# ChangeOverSwitch.net
KiCad netlist of a schematic drawn in EAGLE
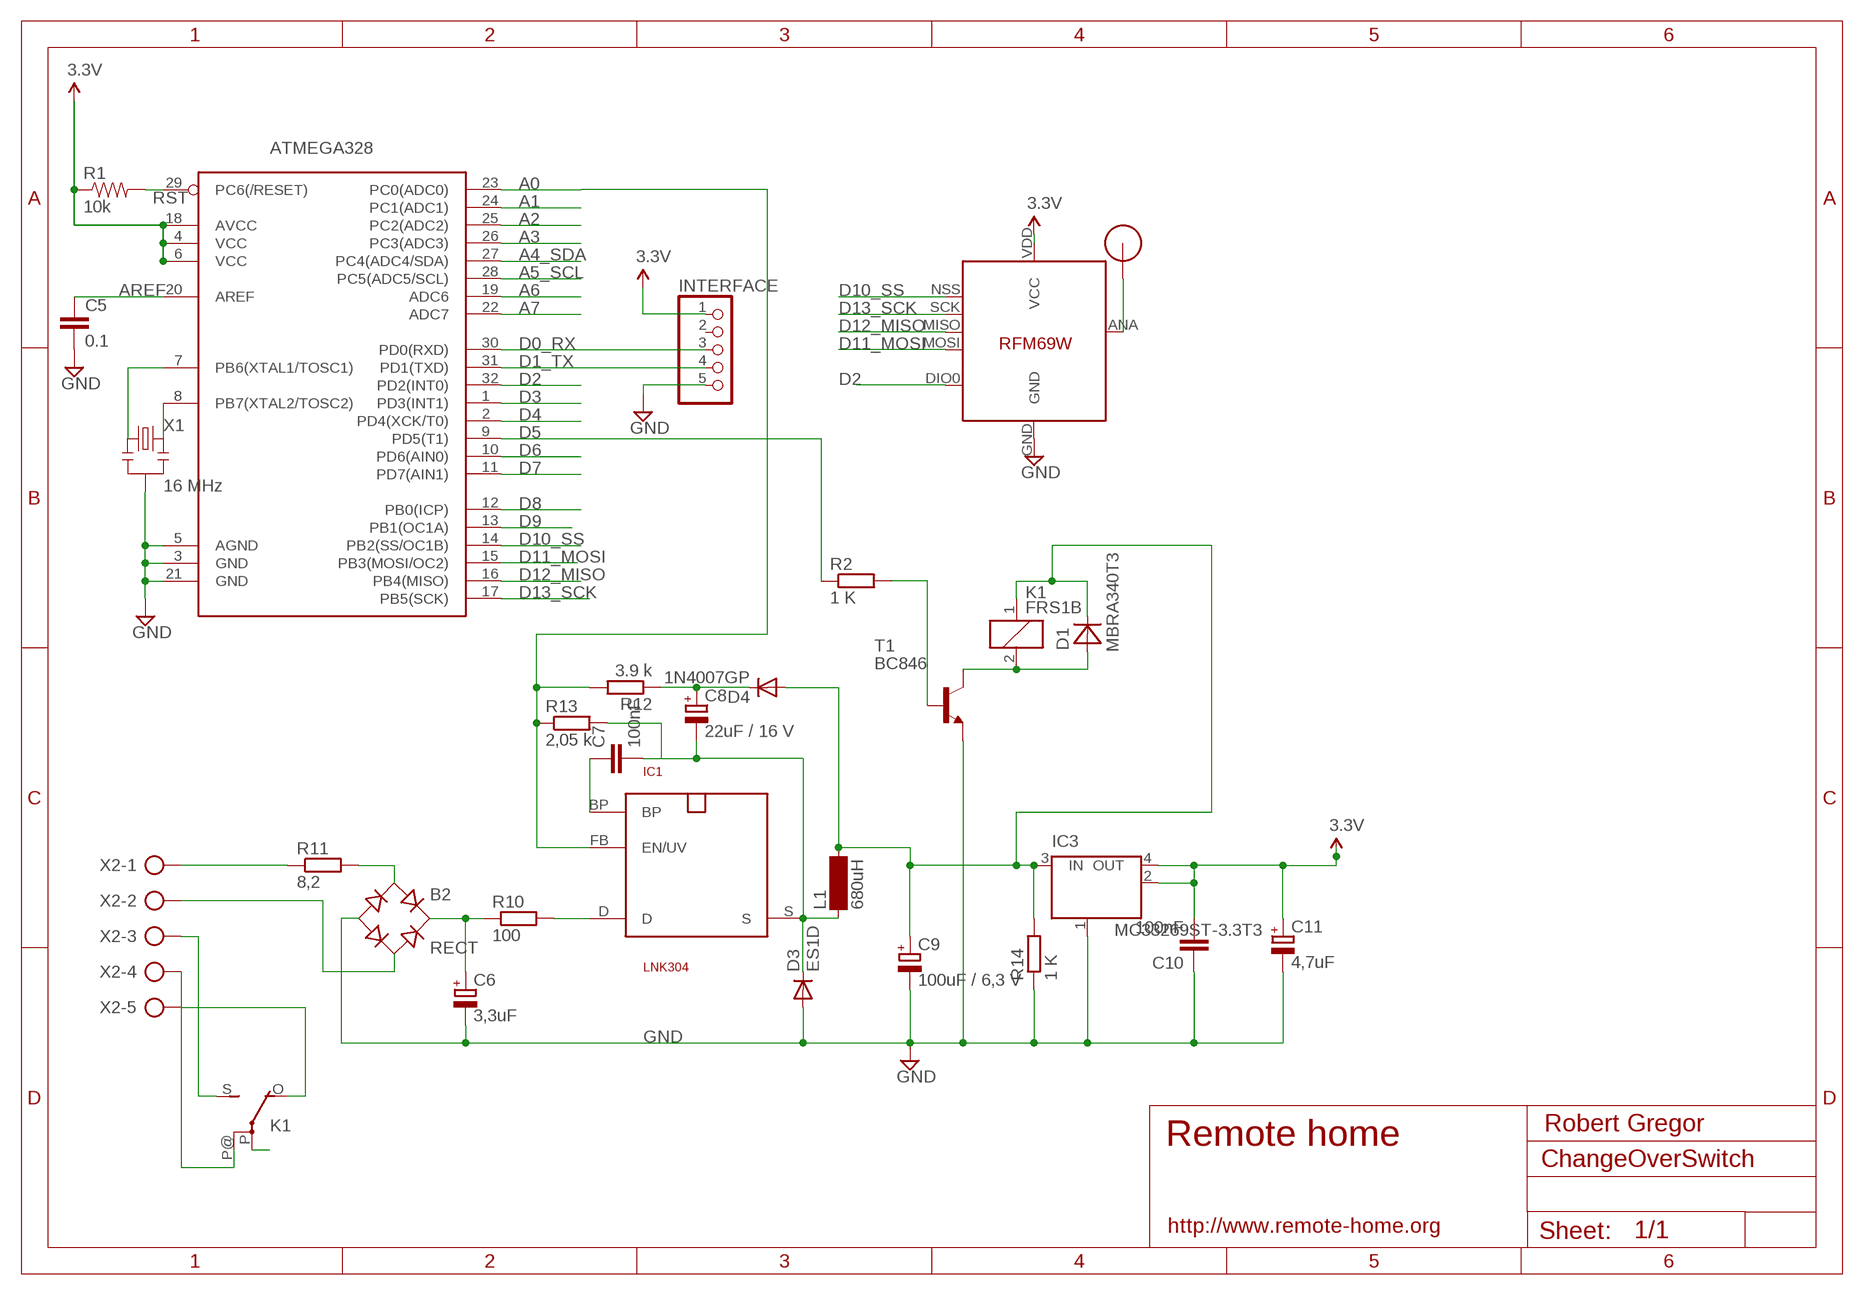
[diagram p0: schematic, sheet 1]

(export (version "E")
  (design (tool "Eeschema 10.0.6"))
  (components
    (comp (ref "ATMEGA328")
      (value "ATMega-328")
      (footprint "eagle-import:TQFP32-08")
      (libsource (lib "eagle-import") (part "ATMEGA168/328TQFP32"))
    )
    (comp (ref "B2")
      (value "RECT")
      (footprint "eagle-import:TO-269AA")
      (libsource (lib "eagle-import") (part "RECTIFIER-S40"))
    )
    (comp (ref "C5")
      (value "0.1")
      (footprint "eagle-import:0603-CAP")
      (libsource (lib "eagle-import") (part "CAP0603-CAP"))
    )
    (comp (ref "C6")
      (value "3,3uF")
      (footprint "eagle-import:E5-10,5")
      (libsource (lib "eagle-import") (part "CPOL-EUE5-10.5"))
    )
    (comp (ref "C7")
      (value "100nF")
      (footprint "eagle-import:C2012")
      (libsource (lib "eagle-import") (part "C-EUC2012"))
    )
    (comp (ref "C8")
      (value "22uF / 16 V")
      (footprint "eagle-import:SMC_C")
      (libsource (lib "eagle-import") (part "CPOL-EUSMCC"))
    )
    (comp (ref "C9")
      (value "100uF / 6,3 V")
      (footprint "eagle-import:E2,5-5")
      (libsource (lib "eagle-import") (part "CPOL-EUE2.5-5"))
    )
    (comp (ref "C10")
      (value "100nF")
      (footprint "eagle-import:C2012")
      (libsource (lib "eagle-import") (part "C-EUC2012"))
    )
    (comp (ref "C11")
      (value "4,7uF")
      (footprint "eagle-import:SMC_A")
      (libsource (lib "eagle-import") (part "CPOL-EUSMCA"))
    )
    (comp (ref "D1")
      (value "MBRA340T3")
      (footprint "eagle-import:SMA")
      (libsource (lib "eagle-import") (part "MBRA340T3"))
    )
    (comp (ref "D3")
      (value "ES1D")
      (footprint "eagle-import:DO214AC")
      (libsource (lib "eagle-import") (part "DIODE-DO214AC"))
    )
    (comp (ref "D4")
      (value "1N4007GP")
      (footprint "eagle-import:DO214AA")
      (libsource (lib "eagle-import") (part "DIODE-DO214AA"))
    )
    (comp (ref "IC1")
      (value "LNK304")
      (footprint "eagle-import:SO-8C")
      (libsource (lib "eagle-import") (part "SO-8C"))
    )
    (comp (ref "IC3")
      (value "MC33269ST-3.3T3")
      (footprint "eagle-import:SOT223")
      (libsource (lib "eagle-import") (part "MC33269ST-3.3T3"))
    )
    (comp (ref "INTERFACE")
      (value "PINHD-1X5")
      (footprint "eagle-import:1X05")
      (libsource (lib "eagle-import") (part "PINHD-1X5"))
    )
    (comp (ref "K1")
      (value "FRS1B")
      (footprint "eagle-import:FRS1B")
      (libsource (lib "eagle-import") (part "FRS1B"))
    )
    (comp (ref "L1")
      (value "680uH")
      (footprint "eagle-import:BS11")
      (libsource (lib "eagle-import") (part "BS11"))
    )
    (comp (ref "R1")
      (value "10k")
      (footprint "eagle-import:0603-RES")
      (libsource (lib "eagle-import") (part "RESISTOR0603-RES"))
    )
    (comp (ref "R2")
      (value "1 K")
      (footprint "eagle-import:M2012")
      (libsource (lib "eagle-import") (part "R-EU_M2012"))
    )
    (comp (ref "R10")
      (value "100")
      (footprint "eagle-import:R2512W")
      (libsource (lib "eagle-import") (part "R-EU_R2512W"))
    )
    (comp (ref "R11")
      (value "8,2")
      (footprint "eagle-import:0411_12")
      (libsource (lib "eagle-import") (part "R-EU_0411/12"))
    )
    (comp (ref "R12")
      (value "3.9 k")
      (footprint "eagle-import:M2012")
      (libsource (lib "eagle-import") (part "R-EU_M2012"))
    )
    (comp (ref "R13")
      (value "2,05 k")
      (footprint "eagle-import:M2012")
      (libsource (lib "eagle-import") (part "R-EU_M2012"))
    )
    (comp (ref "R14")
      (value "1 K")
      (footprint "eagle-import:M2012")
      (libsource (lib "eagle-import") (part "R-EU_M2012"))
    )
    (comp (ref "T1")
      (value "BC846")
      (footprint "eagle-import:SOT23")
      (libsource (lib "eagle-import") (part "BC846"))
    )
    (comp (ref "U$1")
      (value "RFM12B_ANTENNA")
      (footprint "eagle-import:RFM12B-ANTENNA")
      (libsource (lib "eagle-import") (part "RFM12B_ANTENNA"))
    )
    (comp (ref "U$5")
      (value "RFM69")
      (footprint "eagle-import:RFM69W-MINPADS")
      (libsource (lib "eagle-import") (part "RFM69"))
    )
    (comp (ref "X1")
      (value "16 MHz")
      (footprint "eagle-import:RESONATOR-SMD")
      (libsource (lib "eagle-import") (part "RESONATORSMD"))
    )
    (comp (ref "X2")
      (value "AK500/5")
      (footprint "eagle-import:AK500_5")
      (libsource (lib "eagle-import") (part "AK500/5"))
    )
  )
  (nets
    (net (code "1") (name "/A0") (class "Default")
      (node (ref "ATMEGA328") (pin "23") (pinfunction "PC0(ADC0)_23") (pintype "bidirectional"))
      (node (ref "IC1") (pin "FB") (pinfunction "EN/UV_FB") (pintype "input"))
      (node (ref "R12") (pin "2") (pinfunction "2_2") (pintype "passive"))
      (node (ref "R13") (pin "1") (pinfunction "1_1") (pintype "passive"))
    )
    (net (code "2") (name "/A1") (class "Default")
      (node (ref "ATMEGA328") (pin "24") (pinfunction "PC1(ADC1)_24") (pintype "bidirectional"))
    )
    (net (code "3") (name "/A2") (class "Default")
      (node (ref "ATMEGA328") (pin "25") (pinfunction "PC2(ADC2)_25") (pintype "bidirectional"))
    )
    (net (code "4") (name "/A3") (class "Default")
      (node (ref "ATMEGA328") (pin "26") (pinfunction "PC3(ADC3)_26") (pintype "bidirectional"))
    )
    (net (code "5") (name "/A4_SDA") (class "Default")
      (node (ref "ATMEGA328") (pin "27") (pinfunction "PC4(ADC4/SDA)_27") (pintype "bidirectional"))
    )
    (net (code "6") (name "/A5_SCL") (class "Default")
      (node (ref "ATMEGA328") (pin "28") (pinfunction "PC5(ADC5/SCL)_28") (pintype "bidirectional"))
    )
    (net (code "7") (name "/A6") (class "Default")
      (node (ref "ATMEGA328") (pin "19") (pinfunction "ADC6_19") (pintype "bidirectional"))
    )
    (net (code "8") (name "/A7") (class "Default")
      (node (ref "ATMEGA328") (pin "22") (pinfunction "ADC7_22") (pintype "bidirectional"))
    )
    (net (code "9") (name "/AREF") (class "Default")
      (node (ref "ATMEGA328") (pin "20") (pinfunction "AREF_20") (pintype "bidirectional"))
      (node (ref "C5") (pin "1") (pinfunction "1_1") (pintype "passive"))
    )
    (net (code "10") (name "/D0_RX") (class "Default")
      (node (ref "ATMEGA328") (pin "30") (pinfunction "PD0(RXD)_30") (pintype "bidirectional"))
      (node (ref "INTERFACE") (pin "3") (pinfunction "3_3") (pintype "passive"))
    )
    (net (code "11") (name "/D1_TX") (class "Default")
      (node (ref "ATMEGA328") (pin "31") (pinfunction "PD1(TXD)_31") (pintype "bidirectional"))
      (node (ref "INTERFACE") (pin "4") (pinfunction "4_4") (pintype "passive"))
    )
    (net (code "12") (name "/D2") (class "Default")
      (node (ref "ATMEGA328") (pin "32") (pinfunction "PD2(INT0)_32") (pintype "bidirectional"))
      (node (ref "U$5") (pin "DIO0") (pinfunction "DIO0_DIO0") (pintype "open_collector"))
    )
    (net (code "13") (name "/D3") (class "Default")
      (node (ref "ATMEGA328") (pin "1") (pinfunction "PD3(INT1)_1") (pintype "bidirectional"))
    )
    (net (code "14") (name "/D4") (class "Default")
      (node (ref "ATMEGA328") (pin "2") (pinfunction "PD4(XCK/T0)_2") (pintype "bidirectional"))
    )
    (net (code "15") (name "/D5") (class "Default")
      (node (ref "ATMEGA328") (pin "9") (pinfunction "PD5(T1)_9") (pintype "bidirectional"))
      (node (ref "R2") (pin "1") (pinfunction "1_1") (pintype "passive"))
    )
    (net (code "16") (name "/D6") (class "Default")
      (node (ref "ATMEGA328") (pin "10") (pinfunction "PD6(AIN0)_10") (pintype "bidirectional"))
    )
    (net (code "17") (name "/D7") (class "Default")
      (node (ref "ATMEGA328") (pin "11") (pinfunction "PD7(AIN1)_11") (pintype "bidirectional"))
    )
    (net (code "18") (name "/D8") (class "Default")
      (node (ref "ATMEGA328") (pin "12") (pinfunction "PB0(ICP)_12") (pintype "bidirectional"))
    )
    (net (code "19") (name "/D9") (class "Default")
      (node (ref "ATMEGA328") (pin "13") (pinfunction "PB1(OC1A)_13") (pintype "bidirectional"))
    )
    (net (code "20") (name "/D10_SS") (class "Default")
      (node (ref "ATMEGA328") (pin "14") (pinfunction "PB2(SS/OC1B)_14") (pintype "bidirectional"))
      (node (ref "U$5") (pin "NSS") (pinfunction "SEL_NSS") (pintype "input"))
    )
    (net (code "21") (name "/D11_MOSI") (class "Default")
      (node (ref "ATMEGA328") (pin "15") (pinfunction "PB3(MOSI/OC2)_15") (pintype "bidirectional"))
      (node (ref "U$5") (pin "MOSI") (pinfunction "MOSI_MOSI") (pintype "output"))
    )
    (net (code "22") (name "/D12_MISO") (class "Default")
      (node (ref "ATMEGA328") (pin "16") (pinfunction "PB4(MISO)_16") (pintype "bidirectional"))
      (node (ref "U$5") (pin "MISO") (pinfunction "MISO_MISO") (pintype "input"))
    )
    (net (code "23") (name "/D13_SCK") (class "Default")
      (node (ref "ATMEGA328") (pin "17") (pinfunction "PB5(SCK)_17") (pintype "bidirectional"))
      (node (ref "U$5") (pin "SCK") (pinfunction "SCK_SCK") (pintype "input"))
    )
    (net (code "24") (name "/RST") (class "Default")
      (node (ref "ATMEGA328") (pin "29") (pinfunction "PC6(/RESET)_29") (pintype "bidirectional"))
      (node (ref "R1") (pin "2") (pinfunction "2_2") (pintype "passive"))
    )
    (net (code "25") (name "3.3V") (class "Default")
      (node (ref "ATMEGA328") (pin "18") (pinfunction "AVCC_18") (pintype "bidirectional"))
      (node (ref "ATMEGA328") (pin "4") (pinfunction "VCC_4") (pintype "bidirectional"))
      (node (ref "ATMEGA328") (pin "6") (pinfunction "VCC_6") (pintype "bidirectional"))
      (node (ref "C10") (pin "2") (pinfunction "2_2") (pintype "passive"))
      (node (ref "C11") (pin "+") (pinfunction "+_+") (pintype "passive"))
      (node (ref "IC3") (pin "2") (pinfunction "OUT_2") (pintype "passive"))
      (node (ref "IC3") (pin "4") (pinfunction "OUT_4") (pintype "passive"))
      (node (ref "INTERFACE") (pin "1") (pinfunction "1_1") (pintype "passive"))
      (node (ref "R1") (pin "1") (pinfunction "1_1") (pintype "passive"))
      (node (ref "U$5") (pin "VDD") (pinfunction "VCC_VDD") (pintype "power_in"))
    )
    (net (code "26") (name "GND") (class "Default")
      (node (ref "ATMEGA328") (pin "21") (pinfunction "GND_21") (pintype "bidirectional"))
      (node (ref "ATMEGA328") (pin "3") (pinfunction "GND_3") (pintype "bidirectional"))
      (node (ref "ATMEGA328") (pin "5") (pinfunction "AGND_5") (pintype "bidirectional"))
      (node (ref "B2") (pin "-") (pinfunction "-_-") (pintype "passive"))
      (node (ref "C10") (pin "1") (pinfunction "1_1") (pintype "passive"))
      (node (ref "C11") (pin "-") (pinfunction "-_-") (pintype "passive"))
      (node (ref "C5") (pin "2") (pinfunction "2_2") (pintype "passive"))
      (node (ref "C6") (pin "-") (pinfunction "-_-") (pintype "passive"))
      (node (ref "C9") (pin "-") (pinfunction "-_-") (pintype "passive"))
      (node (ref "D3") (pin "A") (pinfunction "A_A") (pintype "passive"))
      (node (ref "IC3") (pin "1") (pinfunction "GND/ADJ_1") (pintype "input"))
      (node (ref "INTERFACE") (pin "5") (pinfunction "5_5") (pintype "passive"))
      (node (ref "R14") (pin "1") (pinfunction "1_1") (pintype "passive"))
      (node (ref "T1") (pin "2") (pinfunction "E_2") (pintype "passive"))
      (node (ref "U$5") (pin "GND") (pinfunction "GND_GND") (pintype "power_in"))
      (node (ref "X1") (pin "2") (pinfunction "2_2") (pintype "passive"))
    )
    (net (code "27") (name "Net-(ATMEGA328-PB6(XTAL1{slash}TOSC1))") (class "Default")
      (node (ref "ATMEGA328") (pin "7") (pinfunction "PB6(XTAL1/TOSC1)_7") (pintype "bidirectional"))
      (node (ref "X1") (pin "1") (pinfunction "1_1") (pintype "passive"))
    )
    (net (code "28") (name "Net-(ATMEGA328-PB7(XTAL2{slash}TOSC2))") (class "Default")
      (node (ref "ATMEGA328") (pin "8") (pinfunction "PB7(XTAL2/TOSC2)_8") (pintype "bidirectional"))
      (node (ref "X1") (pin "3") (pinfunction "3_3") (pintype "passive"))
    )
    (net (code "29") (name "Net-(B2-Pad+)") (class "Default")
      (node (ref "B2") (pin "+") (pinfunction "+_+") (pintype "passive"))
      (node (ref "C6") (pin "+") (pinfunction "+_+") (pintype "passive"))
      (node (ref "R10") (pin "1") (pinfunction "1_1") (pintype "passive"))
    )
    (net (code "30") (name "Net-(B2-PadAC1)") (class "Default")
      (node (ref "B2") (pin "AC1") (pinfunction "AC1_AC1") (pintype "passive"))
      (node (ref "R11") (pin "2") (pinfunction "2_2") (pintype "passive"))
    )
    (net (code "31") (name "Net-(C7-Pad1)") (class "Default")
      (node (ref "C7") (pin "1") (pinfunction "1_1") (pintype "passive"))
      (node (ref "IC1") (pin "BP") (pinfunction "BP_BP") (pintype "passive"))
    )
    (net (code "32") (name "Net-(C7-Pad2)") (class "Default")
      (node (ref "C7") (pin "2") (pinfunction "2_2") (pintype "passive"))
      (node (ref "C8") (pin "-") (pinfunction "-_-") (pintype "passive"))
      (node (ref "D3") (pin "C") (pinfunction "C_C") (pintype "passive"))
      (node (ref "IC1") (pin "S") (pinfunction "S_S") (pintype "power_in"))
      (node (ref "L1") (pin "1") (pinfunction "1_1") (pintype "passive"))
      (node (ref "R13") (pin "2") (pinfunction "2_2") (pintype "passive"))
    )
    (net (code "33") (name "Net-(C8-Pad+)") (class "Default")
      (node (ref "C8") (pin "+") (pinfunction "+_+") (pintype "passive"))
      (node (ref "D4") (pin "C") (pinfunction "C_C") (pintype "passive"))
      (node (ref "R12") (pin "1") (pinfunction "1_1") (pintype "passive"))
    )
    (net (code "34") (name "Net-(IC1-PadD)") (class "Default")
      (node (ref "IC1") (pin "D") (pinfunction "D_D") (pintype "open_collector"))
      (node (ref "R10") (pin "2") (pinfunction "2_2") (pintype "passive"))
    )
    (net (code "35") (name "Net-(IC3-IN)") (class "Default")
      (node (ref "C9") (pin "+") (pinfunction "+_+") (pintype "passive"))
      (node (ref "D1") (pin "C") (pinfunction "C_C") (pintype "passive"))
      (node (ref "D4") (pin "A") (pinfunction "A_A") (pintype "passive"))
      (node (ref "IC3") (pin "3") (pinfunction "IN_3") (pintype "input"))
      (node (ref "K1") (pin "1") (pinfunction "1_1") (pintype "passive"))
      (node (ref "L1") (pin "2") (pinfunction "2_2") (pintype "passive"))
      (node (ref "R14") (pin "2") (pinfunction "2_2") (pintype "passive"))
    )
    (net (code "36") (name "Net-(T1-B)") (class "Default")
      (node (ref "R2") (pin "2") (pinfunction "2_2") (pintype "passive"))
      (node (ref "T1") (pin "1") (pinfunction "B_1") (pintype "passive"))
    )
    (net (code "37") (name "Net-(T1-C)") (class "Default")
      (node (ref "D1") (pin "A") (pinfunction "A_A") (pintype "passive"))
      (node (ref "K1") (pin "2") (pinfunction "2_2") (pintype "passive"))
      (node (ref "T1") (pin "3") (pinfunction "C_3") (pintype "passive"))
    )
    (net (code "38") (name "Net-(U$1-1)") (class "Default")
      (node (ref "U$1") (pin "P$1") (pinfunction "1_P$1") (pintype "bidirectional"))
      (node (ref "U$5") (pin "ANA") (pinfunction "ANT_ANA") (pintype "passive"))
    )
    (net (code "39") (name "Net-(X2A-KL)") (class "Default")
      (node (ref "R11") (pin "1") (pinfunction "1_1") (pintype "passive"))
      (node (ref "X2") (pin "1") (pinfunction "KL_1") (pintype "passive"))
    )
    (net (code "40") (name "Net-(X2B-KL)") (class "Default")
      (node (ref "B2") (pin "AC2") (pinfunction "AC2_AC2") (pintype "passive"))
      (node (ref "X2") (pin "2") (pinfunction "KL_2") (pintype "passive"))
    )
    (net (code "41") (name "Net-(X2C-KL)") (class "Default")
      (node (ref "K1") (pin "S") (pinfunction "S_S") (pintype "passive"))
      (node (ref "X2") (pin "3") (pinfunction "KL_3") (pintype "passive"))
    )
    (net (code "42") (name "Net-(X2D-KL)") (class "Default")
      (node (ref "K1") (pin "P@") (pinfunction "P_P@") (pintype "passive"))
      (node (ref "X2") (pin "4") (pinfunction "KL_4") (pintype "passive"))
    )
    (net (code "43") (name "Net-(X2E-KL)") (class "Default")
      (node (ref "K1") (pin "O") (pinfunction "O_O") (pintype "passive"))
      (node (ref "X2") (pin "5") (pinfunction "KL_5") (pintype "passive"))
    )
    (net (code "44") (name "unconnected-(INTERFACE-Pad2)") (class "Default")
      (node (ref "INTERFACE") (pin "2") (pinfunction "2_2") (pintype "passive"))
    )
    (net (code "45") (name "unconnected-(K1-PadP)") (class "Default")
      (node (ref "K1") (pin "P") (pinfunction "P_P") (pintype "passive"))
    )
  )
)
